# Oxygen-Analyzer.net
KiCad netlist of a schematic drawn in Altium Designer
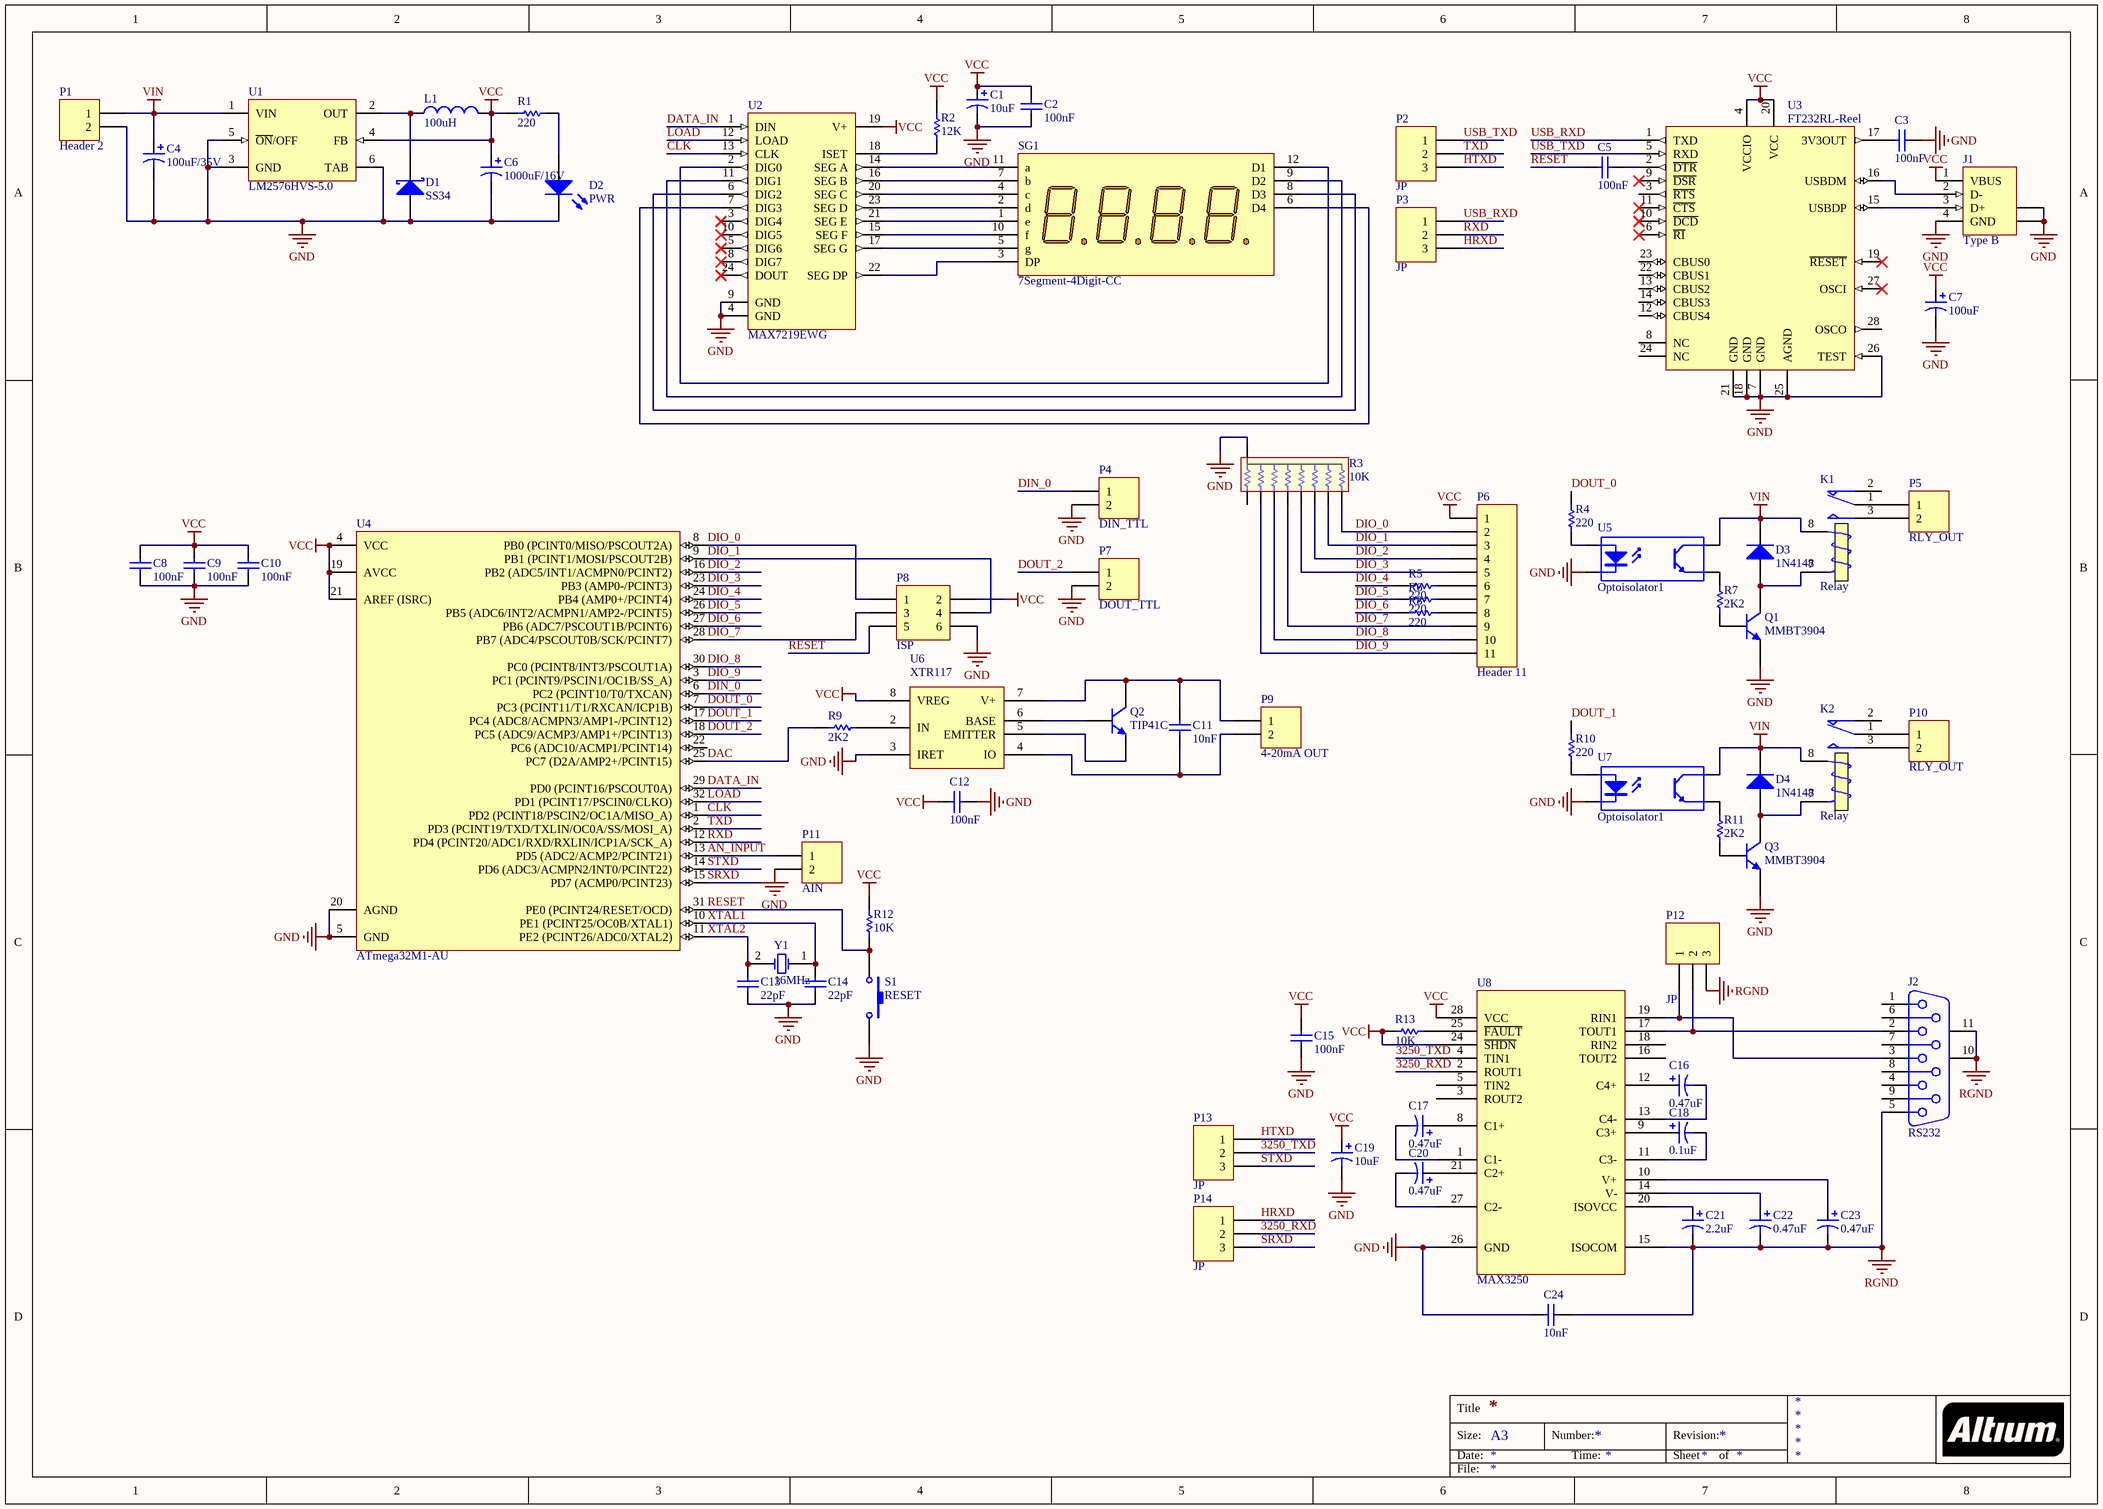
[diagram p0: Oxygen-Analyzer.SchDoc]

(export (version "E")
  (design (tool "Eeschema 10.0.6"))
  (components
    (comp (ref "C1")
      (value "10uF")
      (footprint "toko-Embedded:CT3216")
      (description "Polarized Capacitor (Radial)")
      (fields (field (name "PUBLISHER") "Altium Limited"))
      (libsource (lib "Miscellaneous Devices") (part "Cap Pol1"))
    )
    (comp (ref "C2")
      (value "100nF")
      (footprint "toko-Embedded:C0805")
      (description "Capacitor")
      (fields (field (name "PUBLISHER") "Altium Limited"))
      (libsource (lib "Miscellaneous Devices") (part "Cap"))
    )
    (comp (ref "C3")
      (value "100nF")
      (footprint "toko-Embedded:C0805")
      (description "Capacitor")
      (fields (field (name "PUBLISHER") "Altium Limited"))
      (libsource (lib "Miscellaneous Devices") (part "Cap"))
    )
    (comp (ref "C4")
      (value "100uF/35V")
      (footprint "toko-Embedded:SMD_ELCO_6MM")
      (description "Polarized Capacitor (Radial)")
      (fields (field (name "PUBLISHER") "Altium Limited"))
      (libsource (lib "Miscellaneous Devices") (part "Cap Pol1"))
    )
    (comp (ref "C5")
      (value "100nF")
      (footprint "toko-Embedded:C0805")
      (description "Capacitor")
      (fields (field (name "PUBLISHER") "Altium Limited"))
      (libsource (lib "Miscellaneous Devices") (part "Cap"))
    )
    (comp (ref "C6")
      (value "1000uF/16V")
      (footprint "toko-Embedded:SMD_ELCO_10MM")
      (description "Polarized Capacitor (Radial)")
      (fields (field (name "PUBLISHER") "Altium Limited"))
      (libsource (lib "Miscellaneous Devices") (part "Cap Pol1"))
    )
    (comp (ref "C7")
      (value "100uF")
      (footprint "toko-Embedded:CT7343")
      (description "Polarized Capacitor (Radial)")
      (fields (field (name "PUBLISHER") "Altium Limited"))
      (libsource (lib "Miscellaneous Devices") (part "Cap Pol1"))
    )
    (comp (ref "C8")
      (value "100nF")
      (footprint "toko-Embedded:C0805")
      (description "Capacitor")
      (fields (field (name "PUBLISHER") "Altium Limited"))
      (libsource (lib "Miscellaneous Devices") (part "Cap"))
    )
    (comp (ref "C9")
      (value "100nF")
      (footprint "toko-Embedded:C0805")
      (description "Capacitor")
      (fields (field (name "PUBLISHER") "Altium Limited"))
      (libsource (lib "Miscellaneous Devices") (part "Cap"))
    )
    (comp (ref "C10")
      (value "100nF")
      (footprint "toko-Embedded:C0805")
      (description "Capacitor")
      (fields (field (name "PUBLISHER") "Altium Limited"))
      (libsource (lib "Miscellaneous Devices") (part "Cap"))
    )
    (comp (ref "C11")
      (value "10nF")
      (footprint "toko-Embedded:C0805")
      (description "Capacitor")
      (fields (field (name "PUBLISHER") "Altium Limited"))
      (libsource (lib "Miscellaneous Devices") (part "Cap"))
    )
    (comp (ref "C12")
      (value "100nF")
      (footprint "toko-Embedded:C0805")
      (description "Capacitor")
      (fields (field (name "PUBLISHER") "Altium Limited"))
      (libsource (lib "Miscellaneous Devices") (part "Cap"))
    )
    (comp (ref "C13")
      (value "22pF")
      (footprint "toko-Embedded:C0805")
      (description "Capacitor")
      (fields (field (name "PUBLISHER") "Altium Limited"))
      (libsource (lib "Miscellaneous Devices") (part "Cap"))
    )
    (comp (ref "C14")
      (value "22pF")
      (footprint "toko-Embedded:C0805")
      (description "Capacitor")
      (fields (field (name "PUBLISHER") "Altium Limited"))
      (libsource (lib "Miscellaneous Devices") (part "Cap"))
    )
    (comp (ref "C15")
      (value "100nF")
      (footprint "toko-Embedded:C0805")
      (description "Capacitor")
      (fields (field (name "PUBLISHER") "Altium Limited"))
      (libsource (lib "Miscellaneous Devices") (part "Cap"))
    )
    (comp (ref "C16")
      (value "0.47uF")
      (footprint "toko-Embedded:CT3216")
      (description "Polarized Capacitor (Radial)")
      (fields (field (name "PUBLISHER") "Altium Limited"))
      (libsource (lib "Miscellaneous Devices") (part "Cap Pol1"))
    )
    (comp (ref "C17")
      (value "0.47uF")
      (footprint "toko-Embedded:CT3216")
      (description "Polarized Capacitor (Radial)")
      (fields (field (name "PUBLISHER") "Altium Limited"))
      (libsource (lib "Miscellaneous Devices") (part "Cap Pol1"))
    )
    (comp (ref "C18")
      (value "0.1uF")
      (footprint "toko-Embedded:CT3216")
      (description "Polarized Capacitor (Radial)")
      (fields (field (name "PUBLISHER") "Altium Limited"))
      (libsource (lib "Miscellaneous Devices") (part "Cap Pol1"))
    )
    (comp (ref "C19")
      (value "10uF")
      (footprint "toko-Embedded:CT3216")
      (description "Polarized Capacitor (Radial)")
      (fields (field (name "PUBLISHER") "Altium Limited"))
      (libsource (lib "Miscellaneous Devices") (part "Cap Pol1"))
    )
    (comp (ref "C20")
      (value "0.47uF")
      (footprint "toko-Embedded:CT3216")
      (description "Polarized Capacitor (Radial)")
      (fields (field (name "PUBLISHER") "Altium Limited"))
      (libsource (lib "Miscellaneous Devices") (part "Cap Pol1"))
    )
    (comp (ref "C21")
      (value "2.2uF")
      (footprint "toko-Embedded:CT3216")
      (description "Polarized Capacitor (Radial)")
      (fields (field (name "PUBLISHER") "Altium Limited"))
      (libsource (lib "Miscellaneous Devices") (part "Cap Pol1"))
    )
    (comp (ref "C22")
      (value "0.47uF")
      (footprint "toko-Embedded:CT3216")
      (description "Polarized Capacitor (Radial)")
      (fields (field (name "PUBLISHER") "Altium Limited"))
      (libsource (lib "Miscellaneous Devices") (part "Cap Pol1"))
    )
    (comp (ref "C23")
      (value "0.47uF")
      (footprint "toko-Embedded:CT3216")
      (description "Polarized Capacitor (Radial)")
      (fields (field (name "PUBLISHER") "Altium Limited"))
      (libsource (lib "Miscellaneous Devices") (part "Cap Pol1"))
    )
    (comp (ref "C24")
      (value "10nF")
      (footprint "toko-Embedded:C0805")
      (description "Capacitor")
      (fields (field (name "PUBLISHER") "Altium Limited"))
      (libsource (lib "Miscellaneous Devices") (part "Cap"))
    )
    (comp (ref "D1")
      (value "SS34")
      (footprint "SMC")
      (description "Schottky Diode")
      (fields (field (name "PUBLISHER") "Altium Limited"))
      (libsource (lib "Miscellaneous Devices") (part "D Schottky"))
    )
    (comp (ref "D2")
      (value "PWR")
      (footprint "toko-Embedded:CHIPLED_1206")
      (description "Typical INFRARED GaAs LED")
      (fields (field (name "PUBLISHER") "Altium Limited"))
      (libsource (lib "Miscellaneous Devices") (part "LED0"))
    )
    (comp (ref "D3")
      (value "1N4148")
      (footprint "SOD80C")
      (description "Default Diode")
      (fields (field (name "PUBLISHER") "Altium Limited"))
      (libsource (lib "Miscellaneous Devices") (part "Diode"))
    )
    (comp (ref "D4")
      (value "1N4148")
      (footprint "SOD80C")
      (description "Default Diode")
      (fields (field (name "PUBLISHER") "Altium Limited"))
      (libsource (lib "Miscellaneous Devices") (part "Diode"))
    )
    (comp (ref "J1") (value "Type B") (footprint "USB-B-PTH") (libsource (lib "toko-Embedded") (part "USB")))
    (comp (ref "J2")
      (value "RS232")
      (footprint "toko-Embedded:DB9_MALE")
      (description "Receptacle Assembly, 9 Position, Right Angle")
      (fields (field (name "PUBLISHER") "Altium Limited"))
      (libsource (lib "Miscellaneous Connectors") (part "D Connector 9"))
    )
    (comp (ref "K1")
      (value "Relay")
      (footprint "toko-Embedded:351")
      (description "SPDT Relay")
      (fields (field (name "PUBLISHER") "Altium Limited"))
      (libsource (lib "Miscellaneous Devices") (part "Relay"))
    )
    (comp (ref "K2")
      (value "Relay")
      (footprint "toko-Embedded:351")
      (description "SPDT Relay")
      (fields (field (name "PUBLISHER") "Altium Limited"))
      (libsource (lib "Miscellaneous Devices") (part "Relay"))
    )
    (comp (ref "L1")
      (value "100uH")
      (footprint "DR73")
      (description "Inductor")
      (fields (field (name "PUBLISHER") "Altium Limited"))
      (libsource (lib "Miscellaneous Devices") (part "Inductor"))
    )
    (comp (ref "P1")
      (value "Header 2")
      (footprint "toko-Embedded:W237-132")
      (description "Header, 2-Pin")
      (fields (field (name "PUBLISHER") "Altium Limited"))
      (libsource (lib "") (part "Header 2_1"))
    )
    (comp (ref "P2")
      (value "JP")
      (footprint "HDR1X3")
      (description "Header, 3-Pin")
      (fields (field (name "PUBLISHER") "Altium Limited"))
      (libsource (lib "Miscellaneous Connectors") (part "Header 3"))
    )
    (comp (ref "P3")
      (value "JP")
      (footprint "HDR1X3")
      (description "Header, 3-Pin")
      (fields (field (name "PUBLISHER") "Altium Limited"))
      (libsource (lib "Miscellaneous Connectors") (part "Header 3"))
    )
    (comp (ref "P4")
      (value "DIN_TTL")
      (footprint "toko-Embedded:W237-132")
      (description "Header, 2-Pin")
      (fields (field (name "PUBLISHER") "Altium Limited"))
      (libsource (lib "Miscellaneous Connectors") (part "Header 2"))
    )
    (comp (ref "P5")
      (value "RLY_OUT")
      (footprint "toko-Embedded:W237-132")
      (description "Header, 2-Pin")
      (fields (field (name "PUBLISHER") "Altium Limited"))
      (libsource (lib "Miscellaneous Connectors") (part "Header 2"))
    )
    (comp (ref "P6")
      (value "Header 11")
      (footprint "HDR1X11")
      (description "Header, 11-Pin")
      (fields (field (name "PUBLISHER") "Altium Limited"))
      (libsource (lib "Miscellaneous Connectors") (part "Header 11"))
    )
    (comp (ref "P7")
      (value "DOUT_TTL")
      (footprint "toko-Embedded:W237-132")
      (description "Header, 2-Pin")
      (fields (field (name "PUBLISHER") "Altium Limited"))
      (libsource (lib "Miscellaneous Connectors") (part "Header 2"))
    )
    (comp (ref "P8")
      (value "ISP")
      (footprint "HDR2X3")
      (description "Header, 3-Pin, Dual row")
      (fields (field (name "PUBLISHER") "Altium Limited"))
      (libsource (lib "Miscellaneous Connectors") (part "Header 3X2"))
    )
    (comp (ref "P9")
      (value "4-20mA OUT")
      (footprint "toko-Embedded:W237-132")
      (description "Header, 2-Pin")
      (fields (field (name "PUBLISHER") "Altium Limited"))
      (libsource (lib "Miscellaneous Connectors") (part "Header 2"))
    )
    (comp (ref "P10")
      (value "RLY_OUT")
      (footprint "toko-Embedded:W237-132")
      (description "Header, 2-Pin")
      (fields (field (name "PUBLISHER") "Altium Limited"))
      (libsource (lib "Miscellaneous Connectors") (part "Header 2"))
    )
    (comp (ref "P11")
      (value "AIN")
      (footprint "toko-Embedded:W237-132")
      (description "Header, 2-Pin")
      (fields (field (name "PUBLISHER") "Altium Limited"))
      (libsource (lib "Miscellaneous Connectors") (part "Header 2"))
    )
    (comp (ref "P12")
      (value "JP")
      (footprint "HDR1X3")
      (description "Header, 3-Pin")
      (fields (field (name "PUBLISHER") "Altium Limited"))
      (libsource (lib "") (part "Header 3_1"))
    )
    (comp (ref "P13")
      (value "JP")
      (footprint "HDR1X3")
      (description "Header, 3-Pin")
      (fields (field (name "PUBLISHER") "Altium Limited"))
      (libsource (lib "Miscellaneous Connectors") (part "Header 3"))
    )
    (comp (ref "P14")
      (value "JP")
      (footprint "HDR1X3")
      (description "Header, 3-Pin")
      (fields (field (name "PUBLISHER") "Altium Limited"))
      (libsource (lib "Miscellaneous Connectors") (part "Header 3"))
    )
    (comp (ref "Q1")
      (value "MMBT3904")
      (footprint "SOT23_N")
      (description "NPN Bipolar Transistor")
      (fields (field (name "PUBLISHER") "Altium Limited"))
      (libsource (lib "") (part "NPN_1"))
    )
    (comp (ref "Q2")
      (value "TIP41C")
      (footprint "toko-Embedded:TO220H")
      (description "NPN Bipolar Transistor")
      (fields (field (name "PUBLISHER") "Altium Limited"))
      (libsource (lib "Miscellaneous Devices") (part "NPN"))
    )
    (comp (ref "Q3")
      (value "MMBT3904")
      (footprint "SOT23_N")
      (description "NPN Bipolar Transistor")
      (fields (field (name "PUBLISHER") "Altium Limited"))
      (libsource (lib "") (part "NPN_1"))
    )
    (comp (ref "R1")
      (value "220")
      (footprint "toko-Embedded:R0805")
      (description "Resistor")
      (fields (field (name "PUBLISHER") "Altium Limited"))
      (libsource (lib "Miscellaneous Devices") (part "Res1"))
    )
    (comp (ref "R2")
      (value "12K")
      (footprint "toko-Embedded:R0805")
      (description "Resistor")
      (fields (field (name "PUBLISHER") "Altium Limited"))
      (libsource (lib "Miscellaneous Devices") (part "Res1"))
    )
    (comp (ref "R3")
      (value "10K")
      (footprint "SIL9")
      (libsource (lib "toko-Embedded") (part "Resistor Pack"))
    )
    (comp (ref "R4")
      (value "220")
      (footprint "toko-Embedded:R0805")
      (description "Resistor")
      (fields (field (name "PUBLISHER") "Altium Limited"))
      (libsource (lib "Miscellaneous Devices") (part "Res1"))
    )
    (comp (ref "R5")
      (value "220")
      (footprint "toko-Embedded:R0805")
      (description "Resistor")
      (fields (field (name "PUBLISHER") "Altium Limited"))
      (libsource (lib "Miscellaneous Devices") (part "Res1"))
    )
    (comp (ref "R6")
      (value "220")
      (footprint "toko-Embedded:R0805")
      (description "Resistor")
      (fields (field (name "PUBLISHER") "Altium Limited"))
      (libsource (lib "Miscellaneous Devices") (part "Res1"))
    )
    (comp (ref "R7")
      (value "2K2")
      (footprint "toko-Embedded:R0805")
      (description "Resistor")
      (fields (field (name "PUBLISHER") "Altium Limited"))
      (libsource (lib "Miscellaneous Devices") (part "Res1"))
    )
    (comp (ref "R8")
      (value "220")
      (footprint "toko-Embedded:R0805")
      (description "Resistor")
      (fields (field (name "PUBLISHER") "Altium Limited"))
      (libsource (lib "Miscellaneous Devices") (part "Res1"))
    )
    (comp (ref "R9")
      (value "2K2")
      (footprint "toko-Embedded:R0805")
      (description "Resistor")
      (fields (field (name "PUBLISHER") "Altium Limited"))
      (libsource (lib "Miscellaneous Devices") (part "Res1"))
    )
    (comp (ref "R10")
      (value "220")
      (footprint "toko-Embedded:R0805")
      (description "Resistor")
      (fields (field (name "PUBLISHER") "Altium Limited"))
      (libsource (lib "Miscellaneous Devices") (part "Res1"))
    )
    (comp (ref "R11")
      (value "2K2")
      (footprint "toko-Embedded:R0805")
      (description "Resistor")
      (fields (field (name "PUBLISHER") "Altium Limited"))
      (libsource (lib "Miscellaneous Devices") (part "Res1"))
    )
    (comp (ref "R12")
      (value "10K")
      (footprint "toko-Embedded:R0805")
      (description "Resistor")
      (fields (field (name "PUBLISHER") "Altium Limited"))
      (libsource (lib "Miscellaneous Devices") (part "Res1"))
    )
    (comp (ref "R13")
      (value "10K")
      (footprint "toko-Embedded:R0805")
      (description "Resistor")
      (fields (field (name "PUBLISHER") "Altium Limited"))
      (libsource (lib "Miscellaneous Devices") (part "Res1"))
    )
    (comp (ref "S1")
      (value "RESET")
      (footprint "toko-Embedded:TACTILE-SWITCH-1101NE")
      (description "Switch")
      (fields (field (name "PUBLISHER") "Altium Limited"))
      (libsource (lib "Miscellaneous Devices") (part "SW-PB"))
    )
    (comp (ref "SG1")
      (value "7Segment-4Digit-CC")
      (footprint "7Segment-4Digit-CC")
      (libsource (lib "toko-Embedded") (part "7Segment-4Digit-CC"))
    )
    (comp (ref "U1")
      (value "LM2576HVS-5.0")
      (footprint "TS5B_N")
      (description "SIMPLE SWITCHER® 3A Step-Down Voltage Regulator, 5-pin TO-263")
      (fields
        (field (name "MANUFACTURER") "National Semiconductor")
        (field (name "PUBLISHER") "Altium Limited")
      )
      (libsource (lib "NSC Switcher") (part "LM2576HVS-5.0"))
    )
    (comp (ref "U2")
      (value "MAX7219EWG")
      (footprint "WSO24_N")
      (description "Serially Interfaced, 8-Digit LED Display Driver")
      (fields (field (name "PUBLISHER") "Altium Limited"))
      (libsource (lib "Maxim Interface Display Driver") (part "MAX7219EWG"))
    )
    (comp (ref "U3")
      (value "FT232RL-Reel")
      (footprint "SSOP-28_N")
      (description "USB UART Asynchronous Serial Data Transfer Chip, SSOP-28, Tape and Reel")
      (fields (field (name "PUBLISHER") "Altium Limited"))
      (libsource (lib "FTDI Communication UART") (part "FT232RL-Reel"))
    )
    (comp (ref "U4")
      (value "ATmega32M1-AU")
      (footprint "32A_N")
      (fields (field (name "PUBLISHER") "Altium Limited"))
      (libsource (lib "Atmel Microcontroller 8-Bit Automotive AVR") (part "ATmega32M1-AU"))
    )
    (comp (ref "U5")
      (value "Optoisolator1")
      (footprint "DIP-4")
      (description "4-Pin Phototransistor Optocoupler")
      (fields (field (name "PUBLISHER") "Altium Limited"))
      (libsource (lib "Miscellaneous Devices") (part "Optoisolator1"))
    )
    (comp (ref "U6") (value "XTR117") (footprint "MSOP8") (libsource (lib "toko-Embedded") (part "XTR117")))
    (comp (ref "U7")
      (value "Optoisolator1")
      (footprint "DIP-4")
      (description "4-Pin Phototransistor Optocoupler")
      (fields (field (name "PUBLISHER") "Altium Limited"))
      (libsource (lib "Miscellaneous Devices") (part "Optoisolator1"))
    )
    (comp (ref "U8")
      (value "MAX3250")
      (footprint "SSOP-28")
      (libsource (lib "toko-Embedded") (part "MAX3250"))
    )
    (comp (ref "Y1")
      (value "16MHz")
      (footprint "toko-Embedded:HC49US")
      (description "Crystal Oscillator")
      (fields (field (name "PUBLISHER") "Altium Limited"))
      (libsource (lib "Miscellaneous Devices") (part "XTAL"))
    )
  )
  (nets
    (net (code "1") (name "/3250_RXD") (class "Default")
      (node (ref "P14") (pin "2") (pinfunction "2_2") (pintype "passive"))
      (node (ref "U8") (pin "2") (pinfunction "ROUT1_2") (pintype "passive"))
    )
    (net (code "2") (name "/3250_TXD") (class "Default")
      (node (ref "P13") (pin "2") (pinfunction "2_2") (pintype "passive"))
      (node (ref "U8") (pin "4") (pinfunction "TIN1_4") (pintype "passive"))
    )
    (net (code "3") (name "/AN_INPUT") (class "Default")
      (node (ref "P11") (pin "1") (pinfunction "1_1") (pintype "passive"))
      (node (ref "U4") (pin "13") (pinfunction "PD5_(ADC2/ACMP2/PCINT21)_13") (pintype "bidirectional"))
    )
    (net (code "4") (name "/CLK") (class "Default")
      (node (ref "U2") (pin "13") (pinfunction "CLK_13") (pintype "input"))
      (node (ref "U4") (pin "1") (pinfunction "PD2_(PCINT18/PSCIN2/OC1A/MISO_A)_1") (pintype "bidirectional"))
    )
    (net (code "5") (name "/DAC") (class "Default")
      (node (ref "R9") (pin "1") (pinfunction "1_1") (pintype "passive"))
      (node (ref "U4") (pin "25") (pinfunction "PC7_(D2A/AMP2+/PCINT15)_25") (pintype "bidirectional"))
    )
    (net (code "6") (name "/DATA_IN") (class "Default")
      (node (ref "U2") (pin "1") (pinfunction "DIN_1") (pintype "input"))
      (node (ref "U4") (pin "29") (pinfunction "PD0_(PCINT16/PSCOUT0A)_29") (pintype "bidirectional"))
    )
    (net (code "7") (name "/DIN_0") (class "Default")
      (node (ref "P4") (pin "1") (pinfunction "1_1") (pintype "passive"))
      (node (ref "U4") (pin "6") (pinfunction "PC2_(PCINT10/T0/TXCAN)_6") (pintype "bidirectional"))
    )
    (net (code "8") (name "/DIO_0") (class "Default")
      (node (ref "P6") (pin "2") (pinfunction "2_2") (pintype "passive"))
      (node (ref "P8") (pin "1") (pinfunction "1_1") (pintype "passive"))
      (node (ref "R3") (pin "9") (pinfunction "9_9") (pintype "passive"))
      (node (ref "U4") (pin "8") (pinfunction "PB0_(PCINT0/MISO/PSCOUT2A)_8") (pintype "bidirectional"))
    )
    (net (code "9") (name "/DIO_1") (class "Default")
      (node (ref "P6") (pin "3") (pinfunction "3_3") (pintype "passive"))
      (node (ref "P8") (pin "4") (pinfunction "4_4") (pintype "passive"))
      (node (ref "R3") (pin "8") (pinfunction "8_8") (pintype "passive"))
      (node (ref "U4") (pin "9") (pinfunction "PB1_(PCINT1/MOSI/PSCOUT2B)_9") (pintype "bidirectional"))
    )
    (net (code "10") (name "/DIO_2") (class "Default")
      (node (ref "P6") (pin "4") (pinfunction "4_4") (pintype "passive"))
      (node (ref "R3") (pin "7") (pinfunction "7_7") (pintype "passive"))
      (node (ref "U4") (pin "16") (pinfunction "PB2_(ADC5/INT1/ACMPN0/PCINT2)_16") (pintype "bidirectional"))
    )
    (net (code "11") (name "/DIO_3") (class "Default")
      (node (ref "P6") (pin "5") (pinfunction "5_5") (pintype "passive"))
      (node (ref "R3") (pin "6") (pinfunction "6_6") (pintype "passive"))
      (node (ref "U4") (pin "23") (pinfunction "PB3_(AMP0-/PCINT3)_23") (pintype "bidirectional"))
    )
    (net (code "12") (name "/DIO_4") (class "Default")
      (node (ref "R5") (pin "1") (pinfunction "1_1") (pintype "passive"))
      (node (ref "U4") (pin "24") (pinfunction "PB4_(AMP0+/PCINT4)_24") (pintype "bidirectional"))
    )
    (net (code "13") (name "/DIO_5") (class "Default")
      (node (ref "R6") (pin "1") (pinfunction "1_1") (pintype "passive"))
      (node (ref "U4") (pin "26") (pinfunction "PB5_(ADC6/INT2/ACMPN1/AMP2-/PCINT5)_26") (pintype "bidirectional"))
    )
    (net (code "14") (name "/DIO_6") (class "Default")
      (node (ref "R8") (pin "1") (pinfunction "1_1") (pintype "passive"))
      (node (ref "U4") (pin "27") (pinfunction "PB6_(ADC7/PSCOUT1B/PCINT6)_27") (pintype "bidirectional"))
    )
    (net (code "15") (name "/DIO_7") (class "Default")
      (node (ref "P6") (pin "9") (pinfunction "9_9") (pintype "passive"))
      (node (ref "P8") (pin "3") (pinfunction "3_3") (pintype "passive"))
      (node (ref "R3") (pin "5") (pinfunction "5_5") (pintype "passive"))
      (node (ref "U4") (pin "28") (pinfunction "PB7_(ADC4/PSCOUT0B/SCK/PCINT7)_28") (pintype "bidirectional"))
    )
    (net (code "16") (name "/DIO_8") (class "Default")
      (node (ref "P6") (pin "10") (pinfunction "10_10") (pintype "passive"))
      (node (ref "R3") (pin "4") (pinfunction "4_4") (pintype "passive"))
      (node (ref "U4") (pin "30") (pinfunction "PC0_(PCINT8/INT3/PSCOUT1A)_30") (pintype "bidirectional"))
    )
    (net (code "17") (name "/DIO_9") (class "Default")
      (node (ref "P6") (pin "11") (pinfunction "11_11") (pintype "passive"))
      (node (ref "R3") (pin "3") (pinfunction "3_3") (pintype "passive"))
      (node (ref "U4") (pin "3") (pinfunction "PC1_(PCINT9/PSCIN1/OC1B/SS_A)_3") (pintype "bidirectional"))
    )
    (net (code "18") (name "/DOUT_0") (class "Default")
      (node (ref "R4") (pin "1") (pinfunction "1_1") (pintype "passive"))
      (node (ref "U4") (pin "7") (pinfunction "PC3_(PCINT11/T1/RXCAN/ICP1B)_7") (pintype "bidirectional"))
    )
    (net (code "19") (name "/DOUT_1") (class "Default")
      (node (ref "R10") (pin "1") (pinfunction "1_1") (pintype "passive"))
      (node (ref "U4") (pin "17") (pinfunction "PC4_(ADC8/ACMPN3/AMP1-/PCINT12)_17") (pintype "bidirectional"))
    )
    (net (code "20") (name "/DOUT_2") (class "Default")
      (node (ref "P7") (pin "1") (pinfunction "1_1") (pintype "passive"))
      (node (ref "U4") (pin "18") (pinfunction "PC5_(ADC9/ACMP3/AMP1+/PCINT13)_18") (pintype "bidirectional"))
    )
    (net (code "21") (name "/HRXD") (class "Default")
      (node (ref "P14") (pin "1") (pinfunction "1_1") (pintype "passive"))
      (node (ref "P3") (pin "3") (pinfunction "3_3") (pintype "passive"))
    )
    (net (code "22") (name "/HTXD") (class "Default")
      (node (ref "P13") (pin "1") (pinfunction "1_1") (pintype "passive"))
      (node (ref "P2") (pin "3") (pinfunction "3_3") (pintype "passive"))
    )
    (net (code "23") (name "/LOAD") (class "Default")
      (node (ref "U2") (pin "12") (pinfunction "LOAD_12") (pintype "input"))
      (node (ref "U4") (pin "32") (pinfunction "PD1_(PCINT17/PSCIN0/CLKO)_32") (pintype "bidirectional"))
    )
    (net (code "24") (name "/RESET") (class "Default")
      (node (ref "C5") (pin "2") (pinfunction "2_2") (pintype "passive"))
      (node (ref "P8") (pin "5") (pinfunction "5_5") (pintype "passive"))
      (node (ref "R12") (pin "2") (pinfunction "2_2") (pintype "passive"))
      (node (ref "S1") (pin "1") (pinfunction "1_1") (pintype "passive"))
      (node (ref "U4") (pin "31") (pinfunction "PE0_(PCINT24/RESET/OCD)_31") (pintype "bidirectional"))
    )
    (net (code "25") (name "/RXD") (class "Default")
      (node (ref "P3") (pin "2") (pinfunction "2_2") (pintype "passive"))
      (node (ref "U4") (pin "12") (pinfunction "PD4_(PCINT20/ADC1/RXD/RXLIN/ICP1A/SCK_A)_12") (pintype "bidirectional"))
    )
    (net (code "26") (name "/SRXD") (class "Default")
      (node (ref "P14") (pin "3") (pinfunction "3_3") (pintype "passive"))
      (node (ref "U4") (pin "15") (pinfunction "PD7_(ACMP0/PCINT23)_15") (pintype "bidirectional"))
    )
    (net (code "27") (name "/STXD") (class "Default")
      (node (ref "P13") (pin "3") (pinfunction "3_3") (pintype "passive"))
      (node (ref "U4") (pin "14") (pinfunction "PD6_(ADC3/ACMPN2/INT0/PCINT22)_14") (pintype "bidirectional"))
    )
    (net (code "28") (name "/TXD") (class "Default")
      (node (ref "P2") (pin "2") (pinfunction "2_2") (pintype "passive"))
      (node (ref "U4") (pin "2") (pinfunction "PD3_(PCINT19/TXD/TXLIN/OC0A/SS/MOSI_A)_2") (pintype "bidirectional"))
    )
    (net (code "29") (name "/USB_RXD") (class "Default")
      (node (ref "P3") (pin "1") (pinfunction "1_1") (pintype "passive"))
      (node (ref "U3") (pin "1") (pinfunction "TXD_1") (pintype "output"))
    )
    (net (code "30") (name "/USB_TXD") (class "Default")
      (node (ref "P2") (pin "1") (pinfunction "1_1") (pintype "passive"))
      (node (ref "U3") (pin "5") (pinfunction "RXD_5") (pintype "input"))
    )
    (net (code "31") (name "/XTAL1") (class "Default")
      (node (ref "C14") (pin "2") (pinfunction "2_2") (pintype "passive"))
      (node (ref "U4") (pin "10") (pinfunction "PE1_(PCINT25/OC0B/XTAL1)_10") (pintype "bidirectional"))
      (node (ref "Y1") (pin "1") (pinfunction "OSC1_1") (pintype "passive"))
    )
    (net (code "32") (name "/XTAL2") (class "Default")
      (node (ref "C13") (pin "2") (pinfunction "2_2") (pintype "passive"))
      (node (ref "U4") (pin "11") (pinfunction "PE2_(PCINT26/ADC0/XTAL2)_11") (pintype "bidirectional"))
      (node (ref "Y1") (pin "2") (pinfunction "OSC2_2") (pintype "passive"))
    )
    (net (code "33") (name "GND") (class "Default")
      (node (ref "C1") (pin "2") (pinfunction "2_2") (pintype "passive"))
      (node (ref "C10") (pin "1") (pinfunction "1_1") (pintype "passive"))
      (node (ref "C12") (pin "1") (pinfunction "1_1") (pintype "passive"))
      (node (ref "C13") (pin "1") (pinfunction "1_1") (pintype "passive"))
      (node (ref "C14") (pin "1") (pinfunction "1_1") (pintype "passive"))
      (node (ref "C15") (pin "1") (pinfunction "1_1") (pintype "passive"))
      (node (ref "C19") (pin "2") (pinfunction "2_2") (pintype "passive"))
      (node (ref "C2") (pin "1") (pinfunction "1_1") (pintype "passive"))
      (node (ref "C24") (pin "2") (pinfunction "2_2") (pintype "passive"))
      (node (ref "C3") (pin "1") (pinfunction "1_1") (pintype "passive"))
      (node (ref "C4") (pin "2") (pinfunction "2_2") (pintype "passive"))
      (node (ref "C6") (pin "2") (pinfunction "2_2") (pintype "passive"))
      (node (ref "C7") (pin "2") (pinfunction "2_2") (pintype "passive"))
      (node (ref "C8") (pin "1") (pinfunction "1_1") (pintype "passive"))
      (node (ref "C9") (pin "1") (pinfunction "1_1") (pintype "passive"))
      (node (ref "D1") (pin "1") (pinfunction "A_1") (pintype "passive"))
      (node (ref "D2") (pin "2") (pinfunction "K_2") (pintype "passive"))
      (node (ref "J1") (pin "4") (pinfunction "GND_4") (pintype "power_in"))
      (node (ref "J1") (pin "5") (pinfunction "SHLD_5") (pintype "passive"))
      (node (ref "J1") (pin "6") (pinfunction "SHLD_6") (pintype "passive"))
      (node (ref "P1") (pin "2") (pinfunction "2_2") (pintype "passive"))
      (node (ref "P11") (pin "2") (pinfunction "2_2") (pintype "passive"))
      (node (ref "P4") (pin "2") (pinfunction "2_2") (pintype "passive"))
      (node (ref "P7") (pin "2") (pinfunction "2_2") (pintype "passive"))
      (node (ref "P8") (pin "6") (pinfunction "6_6") (pintype "passive"))
      (node (ref "Q1") (pin "2") (pinfunction "E_2") (pintype "passive"))
      (node (ref "Q3") (pin "2") (pinfunction "E_2") (pintype "passive"))
      (node (ref "R3") (pin "1") (pinfunction "1_1") (pintype "passive"))
      (node (ref "S1") (pin "2") (pinfunction "2_2") (pintype "passive"))
      (node (ref "U1") (pin "3") (pinfunction "GND_3") (pintype "power_in"))
      (node (ref "U1") (pin "5") (pinfunction "~{ON}/OFF_5") (pintype "input"))
      (node (ref "U1") (pin "6") (pinfunction "TAB_6") (pintype "power_in"))
      (node (ref "U2") (pin "4") (pinfunction "GND_4") (pintype "power_in"))
      (node (ref "U2") (pin "9") (pinfunction "GND_9") (pintype "power_in"))
      (node (ref "U3") (pin "18") (pinfunction "GND_18") (pintype "power_in"))
      (node (ref "U3") (pin "21") (pinfunction "GND_21") (pintype "power_in"))
      (node (ref "U3") (pin "25") (pinfunction "AGND_25") (pintype "power_in"))
      (node (ref "U3") (pin "26") (pinfunction "TEST_26") (pintype "input"))
      (node (ref "U3") (pin "7") (pinfunction "GND_7") (pintype "power_in"))
      (node (ref "U4") (pin "20") (pinfunction "AGND_20") (pintype "power_in"))
      (node (ref "U4") (pin "5") (pinfunction "GND_5") (pintype "power_in"))
      (node (ref "U5") (pin "2") (pinfunction "K_2") (pintype "passive"))
      (node (ref "U6") (pin "3") (pinfunction "IRET_3") (pintype "passive"))
      (node (ref "U7") (pin "2") (pinfunction "K_2") (pintype "passive"))
      (node (ref "U8") (pin "26") (pinfunction "GND_26") (pintype "passive"))
    )
    (net (code "34") (name "Net-(D1-K)") (class "Default")
      (node (ref "D1") (pin "2") (pinfunction "K_2") (pintype "passive"))
      (node (ref "L1") (pin "1") (pinfunction "1_1") (pintype "passive"))
      (node (ref "U1") (pin "2") (pinfunction "OUT_2") (pintype "power_in"))
    )
    (net (code "35") (name "Net-(D2-A)") (class "Default")
      (node (ref "D2") (pin "1") (pinfunction "A_1") (pintype "passive"))
      (node (ref "R1") (pin "1") (pinfunction "1_1") (pintype "passive"))
    )
    (net (code "36") (name "Net-(D3-A)") (class "Default")
      (node (ref "D3") (pin "1") (pinfunction "A_1") (pintype "passive"))
      (node (ref "K1") (pin "7") (pinfunction "T2_7") (pintype "passive"))
      (node (ref "Q1") (pin "3") (pinfunction "C_3") (pintype "passive"))
    )
    (net (code "37") (name "Net-(D4-A)") (class "Default")
      (node (ref "D4") (pin "1") (pinfunction "A_1") (pintype "passive"))
      (node (ref "K2") (pin "7") (pinfunction "T2_7") (pintype "passive"))
      (node (ref "Q3") (pin "3") (pinfunction "C_3") (pintype "passive"))
    )
    (net (code "38") (name "Net-(J1-D+)") (class "Default")
      (node (ref "J1") (pin "3") (pinfunction "D+_3") (pintype "input"))
      (node (ref "U3") (pin "15") (pinfunction "USBDP_15") (pintype "bidirectional"))
    )
    (net (code "39") (name "Net-(J1-D-)") (class "Default")
      (node (ref "J1") (pin "2") (pinfunction "D-_2") (pintype "input"))
      (node (ref "U3") (pin "16") (pinfunction "USBDM_16") (pintype "bidirectional"))
    )
    (net (code "40") (name "Net-(K1-COM)") (class "Default")
      (node (ref "K1") (pin "1") (pinfunction "COM_1") (pintype "passive"))
      (node (ref "P5") (pin "1") (pinfunction "1_1") (pintype "passive"))
    )
    (net (code "41") (name "Net-(K1-NO)") (class "Default")
      (node (ref "K1") (pin "3") (pinfunction "NO_3") (pintype "passive"))
      (node (ref "P5") (pin "2") (pinfunction "2_2") (pintype "passive"))
    )
    (net (code "42") (name "Net-(K2-COM)") (class "Default")
      (node (ref "K2") (pin "1") (pinfunction "COM_1") (pintype "passive"))
      (node (ref "P10") (pin "1") (pinfunction "1_1") (pintype "passive"))
    )
    (net (code "43") (name "Net-(K2-NO)") (class "Default")
      (node (ref "K2") (pin "3") (pinfunction "NO_3") (pintype "passive"))
      (node (ref "P10") (pin "2") (pinfunction "2_2") (pintype "passive"))
    )
    (net (code "44") (name "Net-(P6-Pad6)") (class "Default")
      (node (ref "P6") (pin "6") (pinfunction "6_6") (pintype "passive"))
      (node (ref "R5") (pin "2") (pinfunction "2_2") (pintype "passive"))
    )
    (net (code "45") (name "Net-(P6-Pad7)") (class "Default")
      (node (ref "P6") (pin "7") (pinfunction "7_7") (pintype "passive"))
      (node (ref "R6") (pin "2") (pinfunction "2_2") (pintype "passive"))
    )
    (net (code "46") (name "Net-(P6-Pad8)") (class "Default")
      (node (ref "P6") (pin "8") (pinfunction "8_8") (pintype "passive"))
      (node (ref "R8") (pin "2") (pinfunction "2_2") (pintype "passive"))
    )
    (net (code "47") (name "Net-(Q1-B)") (class "Default")
      (node (ref "Q1") (pin "1") (pinfunction "B_1") (pintype "passive"))
      (node (ref "R7") (pin "2") (pinfunction "2_2") (pintype "passive"))
    )
    (net (code "48") (name "Net-(Q2-B)") (class "Default")
      (node (ref "Q2") (pin "1") (pinfunction "B_1") (pintype "passive"))
      (node (ref "U6") (pin "6") (pinfunction "BASE_6") (pintype "passive"))
    )
    (net (code "49") (name "Net-(Q2-C)") (class "Default")
      (node (ref "C11") (pin "2") (pinfunction "2_2") (pintype "passive"))
      (node (ref "P9") (pin "1") (pinfunction "1_1") (pintype "passive"))
      (node (ref "Q2") (pin "2") (pinfunction "C_2") (pintype "passive"))
      (node (ref "U6") (pin "7") (pinfunction "V+_7") (pintype "passive"))
    )
    (net (code "50") (name "Net-(Q2-E)") (class "Default")
      (node (ref "Q2") (pin "3") (pinfunction "E_3") (pintype "passive"))
      (node (ref "U6") (pin "5") (pinfunction "EMITTER_5") (pintype "passive"))
    )
    (net (code "51") (name "Net-(Q3-B)") (class "Default")
      (node (ref "Q3") (pin "1") (pinfunction "B_1") (pintype "passive"))
      (node (ref "R11") (pin "2") (pinfunction "2_2") (pintype "passive"))
    )
    (net (code "52") (name "Net-(SG1-D1)") (class "Default")
      (node (ref "SG1") (pin "12") (pinfunction "D1_12") (pintype "passive"))
      (node (ref "U2") (pin "2") (pinfunction "DIG0_2") (pintype "output"))
    )
    (net (code "53") (name "Net-(SG1-D2)") (class "Default")
      (node (ref "SG1") (pin "9") (pinfunction "D2_9") (pintype "passive"))
      (node (ref "U2") (pin "11") (pinfunction "DIG1_11") (pintype "output"))
    )
    (net (code "54") (name "Net-(SG1-D3)") (class "Default")
      (node (ref "SG1") (pin "8") (pinfunction "D3_8") (pintype "passive"))
      (node (ref "U2") (pin "6") (pinfunction "DIG2_6") (pintype "output"))
    )
    (net (code "55") (name "Net-(SG1-D4)") (class "Default")
      (node (ref "SG1") (pin "6") (pinfunction "D4_6") (pintype "passive"))
      (node (ref "U2") (pin "7") (pinfunction "DIG3_7") (pintype "output"))
    )
    (net (code "56") (name "Net-(SG1-DP)") (class "Default")
      (node (ref "SG1") (pin "3") (pinfunction "DP_3") (pintype "passive"))
      (node (ref "U2") (pin "22") (pinfunction "SEG_DP_22") (pintype "output"))
    )
    (net (code "57") (name "Net-(SG1-a)") (class "Default")
      (node (ref "SG1") (pin "11") (pinfunction "a_11") (pintype "passive"))
      (node (ref "U2") (pin "14") (pinfunction "SEG_A_14") (pintype "output"))
    )
    (net (code "58") (name "Net-(SG1-b)") (class "Default")
      (node (ref "SG1") (pin "7") (pinfunction "b_7") (pintype "passive"))
      (node (ref "U2") (pin "16") (pinfunction "SEG_B_16") (pintype "output"))
    )
    (net (code "59") (name "Net-(SG1-c)") (class "Default")
      (node (ref "SG1") (pin "4") (pinfunction "c_4") (pintype "passive"))
      (node (ref "U2") (pin "20") (pinfunction "SEG_C_20") (pintype "output"))
    )
    (net (code "60") (name "Net-(SG1-d)") (class "Default")
      (node (ref "SG1") (pin "2") (pinfunction "d_2") (pintype "passive"))
      (node (ref "U2") (pin "23") (pinfunction "SEG_D_23") (pintype "output"))
    )
    (net (code "61") (name "Net-(SG1-e)") (class "Default")
      (node (ref "SG1") (pin "1") (pinfunction "e_1") (pintype "passive"))
      (node (ref "U2") (pin "21") (pinfunction "SEG_E_21") (pintype "output"))
    )
    (net (code "62") (name "Net-(SG1-f)") (class "Default")
      (node (ref "SG1") (pin "10") (pinfunction "f_10") (pintype "passive"))
      (node (ref "U2") (pin "15") (pinfunction "SEG_F_15") (pintype "output"))
    )
    (net (code "63") (name "Net-(SG1-g)") (class "Default")
      (node (ref "SG1") (pin "5") (pinfunction "g_5") (pintype "passive"))
      (node (ref "U2") (pin "17") (pinfunction "SEG_G_17") (pintype "output"))
    )
    (net (code "64") (name "Net-(U2-ISET)") (class "Default")
      (node (ref "R2") (pin "2") (pinfunction "2_2") (pintype "passive"))
      (node (ref "U2") (pin "18") (pinfunction "ISET_18") (pintype "passive"))
    )
    (net (code "65") (name "Net-(U3-3V3OUT)") (class "Default")
      (node (ref "C3") (pin "2") (pinfunction "2_2") (pintype "passive"))
      (node (ref "U3") (pin "17") (pinfunction "3V3OUT_17") (pintype "output"))
    )
    (net (code "66") (name "Net-(U3-~{DTR})") (class "Default")
      (node (ref "C5") (pin "1") (pinfunction "1_1") (pintype "passive"))
      (node (ref "U3") (pin "2") (pinfunction "~{DTR}_2") (pintype "output"))
    )
    (net (code "67") (name "Net-(U5-A)") (class "Default")
      (node (ref "R4") (pin "2") (pinfunction "2_2") (pintype "passive"))
      (node (ref "U5") (pin "1") (pinfunction "A_1") (pintype "passive"))
    )
    (net (code "68") (name "Net-(U5-E)") (class "Default")
      (node (ref "R7") (pin "1") (pinfunction "1_1") (pintype "passive"))
      (node (ref "U5") (pin "3") (pinfunction "E_3") (pintype "passive"))
    )
    (net (code "69") (name "Net-(U6-IN)") (class "Default")
      (node (ref "R9") (pin "2") (pinfunction "2_2") (pintype "passive"))
      (node (ref "U6") (pin "2") (pinfunction "IN_2") (pintype "passive"))
    )
    (net (code "70") (name "Net-(U6-IO)") (class "Default")
      (node (ref "C11") (pin "1") (pinfunction "1_1") (pintype "passive"))
      (node (ref "P9") (pin "2") (pinfunction "2_2") (pintype "passive"))
      (node (ref "U6") (pin "4") (pinfunction "IO_4") (pintype "passive"))
    )
    (net (code "71") (name "Net-(U7-A)") (class "Default")
      (node (ref "R10") (pin "2") (pinfunction "2_2") (pintype "passive"))
      (node (ref "U7") (pin "1") (pinfunction "A_1") (pintype "passive"))
    )
    (net (code "72") (name "Net-(U7-E)") (class "Default")
      (node (ref "R11") (pin "1") (pinfunction "1_1") (pintype "passive"))
      (node (ref "U7") (pin "3") (pinfunction "E_3") (pintype "passive"))
    )
    (net (code "73") (name "Net-(U8-C1+)") (class "Default")
      (node (ref "C17") (pin "1") (pinfunction "1_1") (pintype "passive"))
      (node (ref "U8") (pin "8") (pinfunction "C1+_8") (pintype "passive"))
    )
    (net (code "74") (name "Net-(U8-C1-)") (class "Default")
      (node (ref "C17") (pin "2") (pinfunction "2_2") (pintype "passive"))
      (node (ref "U8") (pin "1") (pinfunction "C1-_1") (pintype "passive"))
    )
    (net (code "75") (name "Net-(U8-C2+)") (class "Default")
      (node (ref "C20") (pin "1") (pinfunction "1_1") (pintype "passive"))
      (node (ref "U8") (pin "21") (pinfunction "C2+_21") (pintype "passive"))
    )
    (net (code "76") (name "Net-(U8-C2-)") (class "Default")
      (node (ref "C20") (pin "2") (pinfunction "2_2") (pintype "passive"))
      (node (ref "U8") (pin "27") (pinfunction "C2-_27") (pintype "passive"))
    )
    (net (code "77") (name "Net-(U8-C3+)") (class "Default")
      (node (ref "C18") (pin "1") (pinfunction "1_1") (pintype "passive"))
      (node (ref "U8") (pin "9") (pinfunction "C3+_9") (pintype "passive"))
    )
    (net (code "78") (name "Net-(U8-C3-)") (class "Default")
      (node (ref "C18") (pin "2") (pinfunction "2_2") (pintype "passive"))
      (node (ref "U8") (pin "11") (pinfunction "C3-_11") (pintype "passive"))
    )
    (net (code "79") (name "Net-(U8-C4+)") (class "Default")
      (node (ref "C16") (pin "1") (pinfunction "1_1") (pintype "passive"))
      (node (ref "U8") (pin "12") (pinfunction "C4+_12") (pintype "passive"))
    )
    (net (code "80") (name "Net-(U8-C4-)") (class "Default")
      (node (ref "C16") (pin "2") (pinfunction "2_2") (pintype "passive"))
      (node (ref "U8") (pin "13") (pinfunction "C4-_13") (pintype "passive"))
    )
    (net (code "81") (name "Net-(U8-ISOVCC)") (class "Default")
      (node (ref "C21") (pin "1") (pinfunction "1_1") (pintype "passive"))
      (node (ref "U8") (pin "20") (pinfunction "ISOVCC_20") (pintype "passive"))
    )
    (net (code "82") (name "Net-(U8-RIN1)") (class "Default")
      (node (ref "J2") (pin "3") (pinfunction "3_3") (pintype "passive"))
      (node (ref "P12") (pin "1") (pinfunction "1_1") (pintype "passive"))
      (node (ref "U8") (pin "19") (pinfunction "RIN1_19") (pintype "passive"))
    )
    (net (code "83") (name "Net-(U8-TOUT1)") (class "Default")
      (node (ref "J2") (pin "2") (pinfunction "2_2") (pintype "passive"))
      (node (ref "P12") (pin "2") (pinfunction "2_2") (pintype "passive"))
      (node (ref "U8") (pin "17") (pinfunction "TOUT1_17") (pintype "passive"))
    )
    (net (code "84") (name "Net-(U8-V+)") (class "Default")
      (node (ref "C23") (pin "1") (pinfunction "1_1") (pintype "passive"))
      (node (ref "U8") (pin "10") (pinfunction "V+_10") (pintype "passive"))
    )
    (net (code "85") (name "Net-(U8-V-)") (class "Default")
      (node (ref "C22") (pin "1") (pinfunction "1_1") (pintype "passive"))
      (node (ref "U8") (pin "14") (pinfunction "V-_14") (pintype "passive"))
    )
    (net (code "86") (name "Net-(U8-~{FAULT})") (class "Default")
      (node (ref "R13") (pin "2") (pinfunction "2_2") (pintype "passive"))
      (node (ref "U8") (pin "25") (pinfunction "~{FAULT}_25") (pintype "passive"))
    )
    (net (code "87") (name "RGND") (class "Default")
      (node (ref "C21") (pin "2") (pinfunction "2_2") (pintype "passive"))
      (node (ref "C22") (pin "2") (pinfunction "2_2") (pintype "passive"))
      (node (ref "C23") (pin "2") (pinfunction "2_2") (pintype "passive"))
      (node (ref "C24") (pin "1") (pinfunction "1_1") (pintype "passive"))
      (node (ref "J2") (pin "10") (pinfunction "MH1_10") (pintype "passive"))
      (node (ref "J2") (pin "11") (pinfunction "MH2_11") (pintype "passive"))
      (node (ref "J2") (pin "5") (pinfunction "5_5") (pintype "passive"))
      (node (ref "P12") (pin "3") (pinfunction "3_3") (pintype "passive"))
      (node (ref "U8") (pin "15") (pinfunction "ISOCOM_15") (pintype "passive"))
    )
    (net (code "88") (name "VCC") (class "Default")
      (node (ref "C1") (pin "1") (pinfunction "1_1") (pintype "passive"))
      (node (ref "C10") (pin "2") (pinfunction "2_2") (pintype "passive"))
      (node (ref "C12") (pin "2") (pinfunction "2_2") (pintype "passive"))
      (node (ref "C15") (pin "2") (pinfunction "2_2") (pintype "passive"))
      (node (ref "C19") (pin "1") (pinfunction "1_1") (pintype "passive"))
      (node (ref "C2") (pin "2") (pinfunction "2_2") (pintype "passive"))
      (node (ref "C6") (pin "1") (pinfunction "1_1") (pintype "passive"))
      (node (ref "C7") (pin "1") (pinfunction "1_1") (pintype "passive"))
      (node (ref "C8") (pin "2") (pinfunction "2_2") (pintype "passive"))
      (node (ref "C9") (pin "2") (pinfunction "2_2") (pintype "passive"))
      (node (ref "J1") (pin "1") (pinfunction "VBUS_1") (pintype "power_in"))
      (node (ref "L1") (pin "2") (pinfunction "2_2") (pintype "passive"))
      (node (ref "P6") (pin "1") (pinfunction "1_1") (pintype "passive"))
      (node (ref "P8") (pin "2") (pinfunction "2_2") (pintype "passive"))
      (node (ref "R1") (pin "2") (pinfunction "2_2") (pintype "passive"))
      (node (ref "R12") (pin "1") (pinfunction "1_1") (pintype "passive"))
      (node (ref "R13") (pin "1") (pinfunction "1_1") (pintype "passive"))
      (node (ref "R2") (pin "1") (pinfunction "1_1") (pintype "passive"))
      (node (ref "U1") (pin "4") (pinfunction "FB_4") (pintype "input"))
      (node (ref "U2") (pin "19") (pinfunction "V+_19") (pintype "power_in"))
      (node (ref "U3") (pin "20") (pinfunction "VCC_20") (pintype "power_in"))
      (node (ref "U3") (pin "4") (pinfunction "VCCIO_4") (pintype "power_in"))
      (node (ref "U4") (pin "19") (pinfunction "AVCC_19") (pintype "power_in"))
      (node (ref "U4") (pin "21") (pinfunction "AREF_(ISRC)_21") (pintype "power_in"))
      (node (ref "U4") (pin "4") (pinfunction "VCC_4") (pintype "power_in"))
      (node (ref "U6") (pin "8") (pinfunction "VREG_8") (pintype "passive"))
      (node (ref "U8") (pin "24") (pinfunction "~{SHDN}_24") (pintype "passive"))
      (node (ref "U8") (pin "28") (pinfunction "VCC_28") (pintype "passive"))
    )
    (net (code "89") (name "VIN") (class "Default")
      (node (ref "C4") (pin "1") (pinfunction "1_1") (pintype "passive"))
      (node (ref "D3") (pin "2") (pinfunction "K_2") (pintype "passive"))
      (node (ref "D4") (pin "2") (pinfunction "K_2") (pintype "passive"))
      (node (ref "K1") (pin "8") (pinfunction "T1_8") (pintype "passive"))
      (node (ref "K2") (pin "8") (pinfunction "T1_8") (pintype "passive"))
      (node (ref "P1") (pin "1") (pinfunction "1_1") (pintype "passive"))
      (node (ref "U1") (pin "1") (pinfunction "VIN_1") (pintype "power_in"))
      (node (ref "U5") (pin "4") (pinfunction "C_4") (pintype "passive"))
      (node (ref "U7") (pin "4") (pinfunction "C_4") (pintype "passive"))
    )
    (net (code "90") (name "unconnected-(J2-Pad1)") (class "Default")
      (node (ref "J2") (pin "1") (pinfunction "1_1") (pintype "passive"))
    )
    (net (code "91") (name "unconnected-(J2-Pad4)") (class "Default")
      (node (ref "J2") (pin "4") (pinfunction "4_4") (pintype "passive"))
    )
    (net (code "92") (name "unconnected-(J2-Pad6)") (class "Default")
      (node (ref "J2") (pin "6") (pinfunction "6_6") (pintype "passive"))
    )
    (net (code "93") (name "unconnected-(J2-Pad7)") (class "Default")
      (node (ref "J2") (pin "7") (pinfunction "7_7") (pintype "passive"))
    )
    (net (code "94") (name "unconnected-(J2-Pad8)") (class "Default")
      (node (ref "J2") (pin "8") (pinfunction "8_8") (pintype "passive"))
    )
    (net (code "95") (name "unconnected-(J2-Pad9)") (class "Default")
      (node (ref "J2") (pin "9") (pinfunction "9_9") (pintype "passive"))
    )
    (net (code "96") (name "unconnected-(K1-NC-Pad2)") (class "Default")
      (node (ref "K1") (pin "2") (pinfunction "NC_2") (pintype "passive"))
    )
    (net (code "97") (name "unconnected-(K2-NC-Pad2)") (class "Default")
      (node (ref "K2") (pin "2") (pinfunction "NC_2") (pintype "passive"))
    )
    (net (code "98") (name "unconnected-(R3-Pad2)") (class "Default")
      (node (ref "R3") (pin "2") (pinfunction "2_2") (pintype "passive"))
    )
    (net (code "99") (name "unconnected-(U2-DIG4-Pad3)") (class "Default")
      (node (ref "U2") (pin "3") (pinfunction "DIG4_3") (pintype "output+no_connect"))
    )
    (net (code "100") (name "unconnected-(U2-DIG5-Pad10)") (class "Default")
      (node (ref "U2") (pin "10") (pinfunction "DIG5_10") (pintype "output+no_connect"))
    )
    (net (code "101") (name "unconnected-(U2-DIG6-Pad5)") (class "Default")
      (node (ref "U2") (pin "5") (pinfunction "DIG6_5") (pintype "output+no_connect"))
    )
    (net (code "102") (name "unconnected-(U2-DIG7-Pad8)") (class "Default")
      (node (ref "U2") (pin "8") (pinfunction "DIG7_8") (pintype "output+no_connect"))
    )
    (net (code "103") (name "unconnected-(U2-DOUT-Pad24)") (class "Default")
      (node (ref "U2") (pin "24") (pinfunction "DOUT_24") (pintype "output+no_connect"))
    )
    (net (code "104") (name "unconnected-(U3-CBUS0-Pad23)") (class "Default")
      (node (ref "U3") (pin "23") (pinfunction "CBUS0_23") (pintype "bidirectional"))
    )
    (net (code "105") (name "unconnected-(U3-CBUS1-Pad22)") (class "Default")
      (node (ref "U3") (pin "22") (pinfunction "CBUS1_22") (pintype "bidirectional"))
    )
    (net (code "106") (name "unconnected-(U3-CBUS2-Pad13)") (class "Default")
      (node (ref "U3") (pin "13") (pinfunction "CBUS2_13") (pintype "bidirectional"))
    )
    (net (code "107") (name "unconnected-(U3-CBUS3-Pad14)") (class "Default")
      (node (ref "U3") (pin "14") (pinfunction "CBUS3_14") (pintype "bidirectional"))
    )
    (net (code "108") (name "unconnected-(U3-CBUS4-Pad12)") (class "Default")
      (node (ref "U3") (pin "12") (pinfunction "CBUS4_12") (pintype "bidirectional"))
    )
    (net (code "109") (name "unconnected-(U3-NC-Pad8)") (class "Default")
      (node (ref "U3") (pin "8") (pinfunction "NC_8") (pintype "passive"))
    )
    (net (code "110") (name "unconnected-(U3-NC-Pad24)") (class "Default")
      (node (ref "U3") (pin "24") (pinfunction "NC_24") (pintype "passive"))
    )
    (net (code "111") (name "unconnected-(U3-OSCI-Pad27)") (class "Default")
      (node (ref "U3") (pin "27") (pinfunction "OSCI_27") (pintype "input+no_connect"))
    )
    (net (code "112") (name "unconnected-(U3-OSCO-Pad28)") (class "Default")
      (node (ref "U3") (pin "28") (pinfunction "OSCO_28") (pintype "output"))
    )
    (net (code "113") (name "unconnected-(U3-~{CTS}-Pad11)") (class "Default")
      (node (ref "U3") (pin "11") (pinfunction "~{CTS}_11") (pintype "input+no_connect"))
    )
    (net (code "114") (name "unconnected-(U3-~{DCD}-Pad10)") (class "Default")
      (node (ref "U3") (pin "10") (pinfunction "~{DCD}_10") (pintype "input+no_connect"))
    )
    (net (code "115") (name "unconnected-(U3-~{DSR}-Pad9)") (class "Default")
      (node (ref "U3") (pin "9") (pinfunction "~{DSR}_9") (pintype "input+no_connect"))
    )
    (net (code "116") (name "unconnected-(U3-~{RESET}-Pad19)") (class "Default")
      (node (ref "U3") (pin "19") (pinfunction "~{RESET}_19") (pintype "input+no_connect"))
    )
    (net (code "117") (name "unconnected-(U3-~{RI}-Pad6)") (class "Default")
      (node (ref "U3") (pin "6") (pinfunction "~{RI}_6") (pintype "input+no_connect"))
    )
    (net (code "118") (name "unconnected-(U3-~{RTS}-Pad3)") (class "Default")
      (node (ref "U3") (pin "3") (pinfunction "~{RTS}_3") (pintype "output"))
    )
    (net (code "119") (name "unconnected-(U4-PC6_(ADC10{slash}ACMP1{slash}PCINT14)-Pad22)") (class "Default")
      (node (ref "U4") (pin "22") (pinfunction "PC6_(ADC10/ACMP1/PCINT14)_22") (pintype "bidirectional"))
    )
    (net (code "120") (name "unconnected-(U8-RIN2-Pad18)") (class "Default")
      (node (ref "U8") (pin "18") (pinfunction "RIN2_18") (pintype "passive"))
    )
    (net (code "121") (name "unconnected-(U8-ROUT2-Pad3)") (class "Default")
      (node (ref "U8") (pin "3") (pinfunction "ROUT2_3") (pintype "passive"))
    )
    (net (code "122") (name "unconnected-(U8-TIN2-Pad5)") (class "Default")
      (node (ref "U8") (pin "5") (pinfunction "TIN2_5") (pintype "passive"))
    )
    (net (code "123") (name "unconnected-(U8-TOUT2-Pad16)") (class "Default")
      (node (ref "U8") (pin "16") (pinfunction "TOUT2_16") (pintype "passive"))
    )
  )
)
